# TG-16.net
KiCad netlist of a schematic drawn in EAGLE
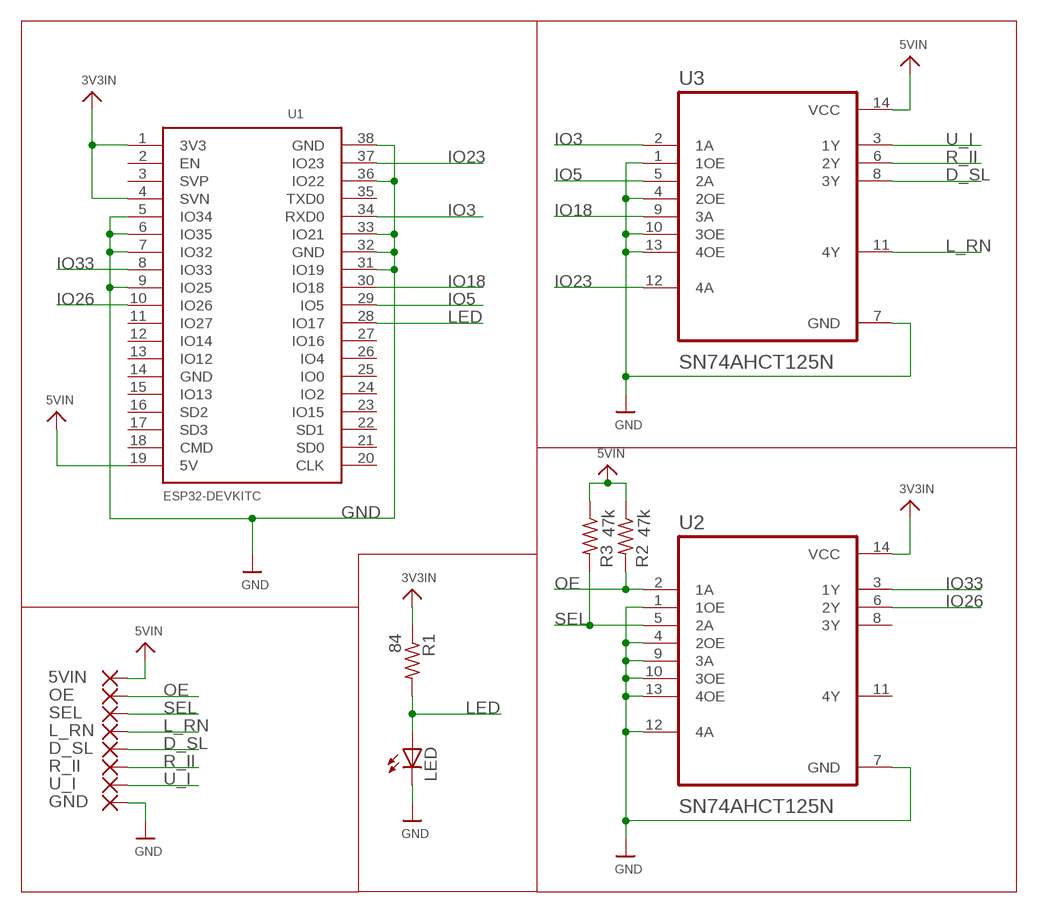
[diagram p0: schematic, sheet 1]

(export (version "E")
  (design (tool "Eeschema 10.0.6"))
  (components
    (comp (ref "5VIN")
      (value "SMD5")
      (footprint "eagle-import:SMD2,54-5,08")
      (libsource (lib "eagle-import") (part "SMD5"))
    )
    (comp (ref "D_SL")
      (value "SMD5")
      (footprint "eagle-import:SMD2,54-5,08")
      (libsource (lib "eagle-import") (part "SMD5"))
    )
    (comp (ref "GND")
      (value "SMD5")
      (footprint "eagle-import:SMD2,54-5,08")
      (libsource (lib "eagle-import") (part "SMD5"))
    )
    (comp (ref "LED")
      (value "LEDCHIPLED_1206")
      (footprint "eagle-import:CHIPLED_1206")
      (libsource (lib "eagle-import") (part "LEDCHIPLED_1206"))
    )
    (comp (ref "L_RN")
      (value "SMD5")
      (footprint "eagle-import:SMD2,54-5,08")
      (libsource (lib "eagle-import") (part "SMD5"))
    )
    (comp (ref "OE")
      (value "SMD5")
      (footprint "eagle-import:SMD2,54-5,08")
      (libsource (lib "eagle-import") (part "SMD5"))
    )
    (comp (ref "R1")
      (value "84")
      (footprint "eagle-import:R1206")
      (libsource (lib "eagle-import") (part "R-US_R1206"))
    )
    (comp (ref "R2")
      (value "47k")
      (footprint "eagle-import:R1206")
      (libsource (lib "eagle-import") (part "adafruit_420_R-US_R1206"))
    )
    (comp (ref "R3")
      (value "47k")
      (footprint "eagle-import:R1206")
      (libsource (lib "eagle-import") (part "adafruit_420_R-US_R1206"))
    )
    (comp (ref "R_II")
      (value "SMD5")
      (footprint "eagle-import:SMD2,54-5,08")
      (libsource (lib "eagle-import") (part "SMD5"))
    )
    (comp (ref "SEL")
      (value "SMD5")
      (footprint "eagle-import:SMD2,54-5,08")
      (libsource (lib "eagle-import") (part "SMD5"))
    )
    (comp (ref "U1")
      (value "ESP32DEVKITC")
      (footprint "eagle-import:ESP32-DEVKITC")
      (libsource (lib "eagle-import") (part "ESP32DEVKITC"))
    )
    (comp (ref "U2")
      (value "SN74AHCT125N")
      (footprint "eagle-import:DIP794W45P254L1969H508Q14")
      (fields (field (name "MF") "Texas Instruments"))
      (libsource (lib "eagle-import") (part "SN74AHCT125N"))
    )
    (comp (ref "U3")
      (value "SN74AHCT125N")
      (footprint "eagle-import:DIP794W45P254L1969H508Q14")
      (fields (field (name "MF") "Texas Instruments"))
      (libsource (lib "eagle-import") (part "SN74AHCT125N"))
    )
    (comp (ref "U_I")
      (value "SMD5")
      (footprint "eagle-import:SMD2,54-5,08")
      (libsource (lib "eagle-import") (part "SMD5"))
    )
  )
  (nets
    (net (code "1") (name "/D_SL") (class "Default")
      (node (ref "D_SL") (pin "1") (pinfunction "P_1") (pintype "passive"))
      (node (ref "U3") (pin "8") (pinfunction "3Y_8") (pintype "output"))
    )
    (net (code "2") (name "/IO3") (class "Default")
      (node (ref "U1") (pin "34") (pinfunction "RXD0_34") (pintype "bidirectional"))
      (node (ref "U3") (pin "2") (pinfunction "1A_2") (pintype "input"))
    )
    (net (code "3") (name "/IO5") (class "Default")
      (node (ref "U1") (pin "29") (pinfunction "IO5_29") (pintype "bidirectional"))
      (node (ref "U3") (pin "5") (pinfunction "2A_5") (pintype "input"))
    )
    (net (code "4") (name "/IO18") (class "Default")
      (node (ref "U1") (pin "30") (pinfunction "IO18_30") (pintype "bidirectional"))
      (node (ref "U3") (pin "9") (pinfunction "3A_9") (pintype "input"))
    )
    (net (code "5") (name "/IO23") (class "Default")
      (node (ref "U1") (pin "37") (pinfunction "IO23_37") (pintype "bidirectional"))
      (node (ref "U3") (pin "12") (pinfunction "4A_12") (pintype "bidirectional"))
    )
    (net (code "6") (name "/IO26") (class "Default")
      (node (ref "U1") (pin "10") (pinfunction "IO26_10") (pintype "bidirectional"))
      (node (ref "U2") (pin "6") (pinfunction "2Y_6") (pintype "output"))
    )
    (net (code "7") (name "/IO33") (class "Default")
      (node (ref "U1") (pin "8") (pinfunction "IO33_8") (pintype "bidirectional"))
      (node (ref "U2") (pin "3") (pinfunction "1Y_3") (pintype "output"))
    )
    (net (code "8") (name "/LED") (class "Default")
      (node (ref "LED") (pin "A") (pinfunction "A_A") (pintype "passive"))
      (node (ref "R1") (pin "2") (pinfunction "2_2") (pintype "passive"))
      (node (ref "U1") (pin "28") (pinfunction "IO17_28") (pintype "bidirectional"))
    )
    (net (code "9") (name "/L_RN") (class "Default")
      (node (ref "L_RN") (pin "1") (pinfunction "P_1") (pintype "passive"))
      (node (ref "U3") (pin "11") (pinfunction "4Y_11") (pintype "output"))
    )
    (net (code "10") (name "/OE") (class "Default")
      (node (ref "OE") (pin "1") (pinfunction "P_1") (pintype "passive"))
      (node (ref "R2") (pin "2") (pinfunction "2_2") (pintype "passive"))
      (node (ref "U2") (pin "2") (pinfunction "1A_2") (pintype "input"))
    )
    (net (code "11") (name "/R_II") (class "Default")
      (node (ref "R_II") (pin "1") (pinfunction "P_1") (pintype "passive"))
      (node (ref "U3") (pin "6") (pinfunction "2Y_6") (pintype "output"))
    )
    (net (code "12") (name "/SEL") (class "Default")
      (node (ref "R3") (pin "2") (pinfunction "2_2") (pintype "passive"))
      (node (ref "SEL") (pin "1") (pinfunction "P_1") (pintype "passive"))
      (node (ref "U2") (pin "5") (pinfunction "2A_5") (pintype "input"))
    )
    (net (code "13") (name "/U_I") (class "Default")
      (node (ref "U3") (pin "3") (pinfunction "1Y_3") (pintype "output"))
      (node (ref "U_I") (pin "1") (pinfunction "P_1") (pintype "passive"))
    )
    (net (code "14") (name "3V3IN") (class "Default")
      (node (ref "R1") (pin "1") (pinfunction "1_1") (pintype "passive"))
      (node (ref "U1") (pin "1") (pinfunction "3V3_1") (pintype "bidirectional"))
      (node (ref "U1") (pin "4") (pinfunction "SVN_4") (pintype "bidirectional"))
      (node (ref "U2") (pin "14") (pinfunction "VCC_14") (pintype "power_in"))
    )
    (net (code "15") (name "5VIN") (class "Default")
      (node (ref "5VIN") (pin "1") (pinfunction "P_1") (pintype "passive"))
      (node (ref "R2") (pin "1") (pinfunction "1_1") (pintype "passive"))
      (node (ref "R3") (pin "1") (pinfunction "1_1") (pintype "passive"))
      (node (ref "U1") (pin "19") (pinfunction "5V_19") (pintype "bidirectional"))
      (node (ref "U3") (pin "14") (pinfunction "VCC_14") (pintype "power_in"))
    )
    (net (code "16") (name "GND") (class "Default")
      (node (ref "GND") (pin "1") (pinfunction "P_1") (pintype "passive"))
      (node (ref "LED") (pin "C") (pinfunction "C_C") (pintype "passive"))
      (node (ref "U1") (pin "31") (pinfunction "IO19_31") (pintype "bidirectional"))
      (node (ref "U1") (pin "32") (pinfunction "GND_32") (pintype "bidirectional"))
      (node (ref "U1") (pin "33") (pinfunction "IO21_33") (pintype "bidirectional"))
      (node (ref "U1") (pin "36") (pinfunction "IO22_36") (pintype "bidirectional"))
      (node (ref "U1") (pin "38") (pinfunction "GND_38") (pintype "bidirectional"))
      (node (ref "U1") (pin "5") (pinfunction "IO34_5") (pintype "bidirectional"))
      (node (ref "U1") (pin "6") (pinfunction "IO35_6") (pintype "bidirectional"))
      (node (ref "U1") (pin "7") (pinfunction "IO32_7") (pintype "bidirectional"))
      (node (ref "U1") (pin "9") (pinfunction "IO25_9") (pintype "bidirectional"))
      (node (ref "U2") (pin "1") (pinfunction "1OE_1") (pintype "input"))
      (node (ref "U2") (pin "10") (pinfunction "3OE_10") (pintype "input"))
      (node (ref "U2") (pin "12") (pinfunction "4A_12") (pintype "bidirectional"))
      (node (ref "U2") (pin "13") (pinfunction "4OE_13") (pintype "input"))
      (node (ref "U2") (pin "4") (pinfunction "2OE_4") (pintype "input"))
      (node (ref "U2") (pin "7") (pinfunction "GND_7") (pintype "power_in"))
      (node (ref "U2") (pin "9") (pinfunction "3A_9") (pintype "input"))
      (node (ref "U3") (pin "1") (pinfunction "1OE_1") (pintype "input"))
      (node (ref "U3") (pin "10") (pinfunction "3OE_10") (pintype "input"))
      (node (ref "U3") (pin "13") (pinfunction "4OE_13") (pintype "input"))
      (node (ref "U3") (pin "4") (pinfunction "2OE_4") (pintype "input"))
      (node (ref "U3") (pin "7") (pinfunction "GND_7") (pintype "power_in"))
    )
    (net (code "17") (name "unconnected-(U1-CLK-Pad20)") (class "Default")
      (node (ref "U1") (pin "20") (pinfunction "CLK_20") (pintype "bidirectional"))
    )
    (net (code "18") (name "unconnected-(U1-CMD-Pad18)") (class "Default")
      (node (ref "U1") (pin "18") (pinfunction "CMD_18") (pintype "bidirectional"))
    )
    (net (code "19") (name "unconnected-(U1-EN-Pad2)") (class "Default")
      (node (ref "U1") (pin "2") (pinfunction "EN_2") (pintype "bidirectional"))
    )
    (net (code "20") (name "unconnected-(U1-GND-Pad14)") (class "Default")
      (node (ref "U1") (pin "14") (pinfunction "GND_14") (pintype "bidirectional"))
    )
    (net (code "21") (name "unconnected-(U1-IO0-Pad25)") (class "Default")
      (node (ref "U1") (pin "25") (pinfunction "IO0_25") (pintype "bidirectional"))
    )
    (net (code "22") (name "unconnected-(U1-IO2-Pad24)") (class "Default")
      (node (ref "U1") (pin "24") (pinfunction "IO2_24") (pintype "bidirectional"))
    )
    (net (code "23") (name "unconnected-(U1-IO4-Pad26)") (class "Default")
      (node (ref "U1") (pin "26") (pinfunction "IO4_26") (pintype "bidirectional"))
    )
    (net (code "24") (name "unconnected-(U1-IO12-Pad13)") (class "Default")
      (node (ref "U1") (pin "13") (pinfunction "IO12_13") (pintype "bidirectional"))
    )
    (net (code "25") (name "unconnected-(U1-IO13-Pad15)") (class "Default")
      (node (ref "U1") (pin "15") (pinfunction "IO13_15") (pintype "bidirectional"))
    )
    (net (code "26") (name "unconnected-(U1-IO14-Pad12)") (class "Default")
      (node (ref "U1") (pin "12") (pinfunction "IO14_12") (pintype "bidirectional"))
    )
    (net (code "27") (name "unconnected-(U1-IO15-Pad23)") (class "Default")
      (node (ref "U1") (pin "23") (pinfunction "IO15_23") (pintype "bidirectional"))
    )
    (net (code "28") (name "unconnected-(U1-IO16-Pad27)") (class "Default")
      (node (ref "U1") (pin "27") (pinfunction "IO16_27") (pintype "bidirectional"))
    )
    (net (code "29") (name "unconnected-(U1-IO27-Pad11)") (class "Default")
      (node (ref "U1") (pin "11") (pinfunction "IO27_11") (pintype "bidirectional"))
    )
    (net (code "30") (name "unconnected-(U1-SD0-Pad21)") (class "Default")
      (node (ref "U1") (pin "21") (pinfunction "SD0_21") (pintype "bidirectional"))
    )
    (net (code "31") (name "unconnected-(U1-SD1-Pad22)") (class "Default")
      (node (ref "U1") (pin "22") (pinfunction "SD1_22") (pintype "bidirectional"))
    )
    (net (code "32") (name "unconnected-(U1-SD2-Pad16)") (class "Default")
      (node (ref "U1") (pin "16") (pinfunction "SD2_16") (pintype "bidirectional"))
    )
    (net (code "33") (name "unconnected-(U1-SD3-Pad17)") (class "Default")
      (node (ref "U1") (pin "17") (pinfunction "SD3_17") (pintype "bidirectional"))
    )
    (net (code "34") (name "unconnected-(U1-SVP-Pad3)") (class "Default")
      (node (ref "U1") (pin "3") (pinfunction "SVP_3") (pintype "bidirectional"))
    )
    (net (code "35") (name "unconnected-(U1-TXD0-Pad35)") (class "Default")
      (node (ref "U1") (pin "35") (pinfunction "TXD0_35") (pintype "bidirectional"))
    )
    (net (code "36") (name "unconnected-(U2-3Y-Pad8)") (class "Default")
      (node (ref "U2") (pin "8") (pinfunction "3Y_8") (pintype "output"))
    )
    (net (code "37") (name "unconnected-(U2-4Y-Pad11)") (class "Default")
      (node (ref "U2") (pin "11") (pinfunction "4Y_11") (pintype "output"))
    )
  )
)
